# led-relay.net
KiCad netlist of a schematic drawn in Altium Designer
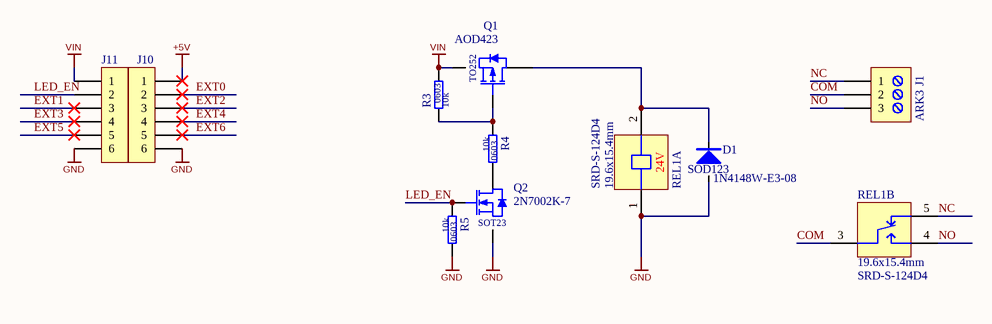
[diagram p0: led-relay.SchDoc]

(export (version "E")
  (design (tool "Eeschema 10.0.6"))
  (components
    (comp (ref "D1")
      (value "1N4148W-E3-08")
      (footprint "SOD123")
      (fields
        (field (name "SCH_FOOTPRINT") "SOD123")
        (field (name "PART NUMBER") "D_1N4148W_0A15_75V_SOD123")
        (field (name "VOLTAGE") "75")
        (field (name "MANUFACTURER") "Vishay")
      )
      (libsource (lib "Library") (part "D"))
    )
    (comp (ref "J1")
      (value "ARK3")
      (footprint "J_ARK3")
      (description "ARK Screw terminal, 3-Pin")
      (fields
        (field (name "SCH_FOOTPRINT") "ARK3")
        (field (name "PART NUMBER") "J_TB-5.0-P-3P")
        (field (name "MANUFACTURER") "DEGSON ELECTRONICS")
      )
      (libsource (lib "Library") (part "J_ARK3"))
    )
    (comp (ref "J10")
      (value "Goldpin")
      (footprint "P_HEADER_1x6_2.54")
      (description "Pin Header")
      (fields (field (name "PART NUMBER") "P_HEADER_1x6_2.54") (field (name "MANUFACTURER") "Connfly"))
      (libsource (lib "") (part "P_HEADER_1x6_1"))
    )
    (comp (ref "J11")
      (value "Goldpin")
      (footprint "P_HEADER_1x6_2.54")
      (description "Pin Header")
      (fields (field (name "PART NUMBER") "P_HEADER_1x6_2.54") (field (name "MANUFACTURER") "Connfly"))
      (libsource (lib "Library") (part "P_HEADER_1x6"))
    )
    (comp (ref "Q1")
      (value "AOD423")
      (footprint "DPAK_TO252-3_SC63_M")
      (fields
        (field (name "SCH_FOOTPRINT") "TO252")
        (field (name "PART NUMBER") "QP_AOD423")
        (field (name "VOLTAGE") "30V")
        (field (name "MANUFACTURER") "Alpha&Omega Semiconductor")
      )
      (libsource (lib "Library") (part "QP_GDS"))
    )
    (comp (ref "Q2")
      (value "2N7002K-7")
      (footprint "SOT23_TO236_SC59")
      (fields
        (field (name "SCH_FOOTPRINT") "SOT23")
        (field (name "PART NUMBER") "QN_2N7002K-7")
        (field (name "VOLTAGE") "60V")
        (field (name "MANUFACTURER") "Diodes Inc")
      )
      (libsource (lib "Library") (part "QN_GSD"))
    )
    (comp (ref "R3")
      (value "10k")
      (footprint "R_0603_1608")
      (fields
        (field (name "SCH_FOOTPRINT") "0603")
        (field (name "PART NUMBER") "R_10k_0603_1")
        (field (name "VOLTAGE") "75V")
        (field (name "POWER") "100mW")
      )
      (libsource (lib "Library") (part "R"))
    )
    (comp (ref "R4")
      (value "10k")
      (footprint "R_0603_1608")
      (fields
        (field (name "SCH_FOOTPRINT") "0603")
        (field (name "PART NUMBER") "R_10k_0603_1")
        (field (name "VOLTAGE") "75V")
        (field (name "POWER") "100mW")
      )
      (libsource (lib "Library") (part "R"))
    )
    (comp (ref "R5")
      (value "10k")
      (footprint "R_0603_1608")
      (fields
        (field (name "SCH_FOOTPRINT") "0603")
        (field (name "PART NUMBER") "R_10k_0603_1")
        (field (name "VOLTAGE") "75V")
        (field (name "POWER") "100mW")
      )
      (libsource (lib "Library") (part "R"))
    )
    (comp (ref "REL1")
      (value "SRD-S-124D4")
      (footprint "SRD-S-124D4")
      (fields
        (field (name "SCH_FOOTPRINT") "19.6x15.4mm")
        (field (name "PART NUMBER") "REL_SRD-S-124D4")
        (field (name "VOLTAGE") "24V")
        (field (name "MANUFACTURER") "Sanyou")
      )
      (libsource (lib "Library") (part "REL_SRD-S-124D4"))
    )
  )
  (nets
    (net (code "1") (name "+5V") (class "Default")
      (node (ref "J10") (pin "1") (pinfunction "1_1") (pintype "passive"))
    )
    (net (code "2") (name "/COM") (class "Default")
      (node (ref "J1") (pin "2") (pinfunction "2_2") (pintype "passive"))
      (node (ref "REL1") (pin "3") (pinfunction "3_3") (pintype "passive"))
    )
    (net (code "3") (name "/EXT0") (class "Default")
      (node (ref "J10") (pin "2") (pinfunction "2_2") (pintype "passive+no_connect"))
    )
    (net (code "4") (name "/EXT1") (class "Default")
      (node (ref "J11") (pin "3") (pinfunction "3_3") (pintype "passive+no_connect"))
    )
    (net (code "5") (name "/EXT2") (class "Default")
      (node (ref "J10") (pin "3") (pinfunction "3_3") (pintype "passive+no_connect"))
    )
    (net (code "6") (name "/EXT3") (class "Default")
      (node (ref "J11") (pin "4") (pinfunction "4_4") (pintype "passive+no_connect"))
    )
    (net (code "7") (name "/EXT4") (class "Default")
      (node (ref "J10") (pin "4") (pinfunction "4_4") (pintype "passive+no_connect"))
    )
    (net (code "8") (name "/EXT5") (class "Default")
      (node (ref "J11") (pin "5") (pinfunction "5_5") (pintype "passive+no_connect"))
    )
    (net (code "9") (name "/EXT6") (class "Default")
      (node (ref "J10") (pin "5") (pinfunction "5_5") (pintype "passive+no_connect"))
    )
    (net (code "10") (name "/LED_EN") (class "Default")
      (node (ref "J11") (pin "2") (pinfunction "2_2") (pintype "passive"))
      (node (ref "Q2") (pin "1") (pinfunction "G_1") (pintype "passive"))
      (node (ref "R5") (pin "1") (pinfunction "1_1") (pintype "passive"))
    )
    (net (code "11") (name "/NC") (class "Default")
      (node (ref "J1") (pin "1") (pinfunction "1_1") (pintype "passive"))
      (node (ref "REL1") (pin "5") (pinfunction "5_5") (pintype "passive"))
    )
    (net (code "12") (name "/NO") (class "Default")
      (node (ref "J1") (pin "3") (pinfunction "3_3") (pintype "passive"))
      (node (ref "REL1") (pin "4") (pinfunction "8_4") (pintype "passive"))
    )
    (net (code "13") (name "GND") (class "Default")
      (node (ref "D1") (pin "2") (pintype "passive"))
      (node (ref "J10") (pin "6") (pinfunction "6_6") (pintype "passive"))
      (node (ref "J11") (pin "6") (pinfunction "6_6") (pintype "passive"))
      (node (ref "Q2") (pin "2") (pinfunction "S_2") (pintype "passive"))
      (node (ref "R5") (pin "2") (pinfunction "2_2") (pintype "passive"))
      (node (ref "REL1") (pin "1") (pinfunction "1_1") (pintype "passive"))
    )
    (net (code "14") (name "Net-(Q1-D)") (class "Default")
      (node (ref "D1") (pin "1") (pintype "passive"))
      (node (ref "Q1") (pin "2") (pinfunction "D_2") (pintype "passive"))
      (node (ref "REL1") (pin "2") (pinfunction "2_2") (pintype "passive"))
    )
    (net (code "15") (name "Net-(Q1-G)") (class "Default")
      (node (ref "Q1") (pin "1") (pinfunction "G_1") (pintype "passive"))
      (node (ref "R3") (pin "1") (pinfunction "1_1") (pintype "passive"))
      (node (ref "R4") (pin "1") (pinfunction "1_1") (pintype "passive"))
    )
    (net (code "16") (name "Net-(Q2-D)") (class "Default")
      (node (ref "Q2") (pin "3") (pinfunction "D_3") (pintype "passive"))
      (node (ref "R4") (pin "2") (pinfunction "2_2") (pintype "passive"))
    )
    (net (code "17") (name "VIN") (class "Default")
      (node (ref "J11") (pin "1") (pinfunction "1_1") (pintype "passive"))
      (node (ref "Q1") (pin "3") (pinfunction "S_3") (pintype "passive"))
      (node (ref "R3") (pin "2") (pinfunction "2_2") (pintype "passive"))
    )
  )
)
